# RFM232_V08_USB.net
KiCad netlist of a schematic drawn in Altium Designer
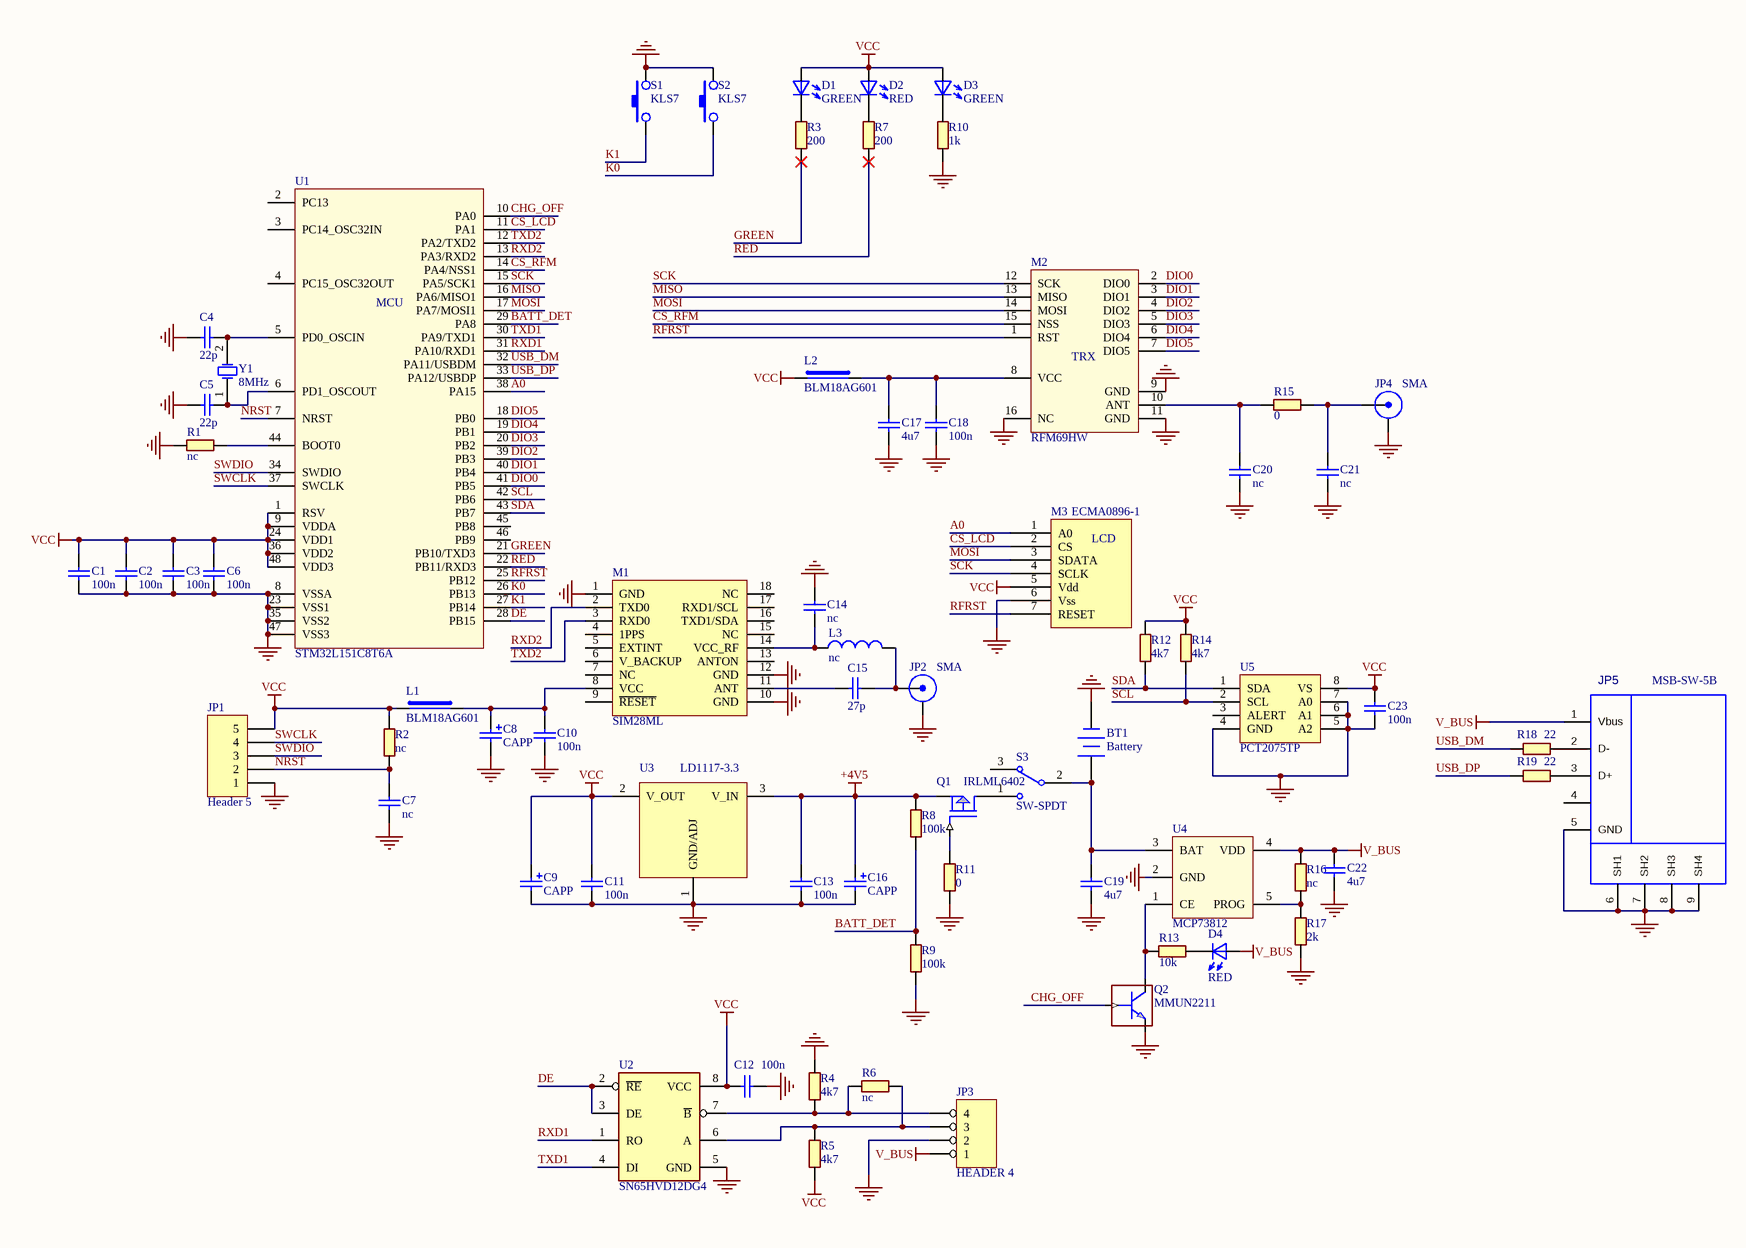
[diagram p0: RFM232_V08_USB.SchDoc]

(export (version "E")
  (design (tool "Eeschema 10.0.6"))
  (components
    (comp (ref "BT1")
      (value "Battery")
      (footprint "18650")
      (description "Multicell Battery")
      (fields (field (name "PUBLISHER") "Altium Limited"))
      (libsource (lib "Miscellaneous Devices") (part "Battery"))
    )
    (comp (ref "C1") (value "100n") (footprint "C-0603") (libsource (lib "Discrete") (part "CAPN")))
    (comp (ref "C2") (value "100n") (footprint "C-0603") (libsource (lib "Discrete") (part "CAPN")))
    (comp (ref "C3") (value "100n") (footprint "C-0603") (libsource (lib "Discrete") (part "CAPN")))
    (comp (ref "C4") (value "22p") (footprint "C-0603") (libsource (lib "Discrete") (part "CAPN")))
    (comp (ref "C5") (value "22p") (footprint "C-0603") (libsource (lib "Discrete") (part "CAPN")))
    (comp (ref "C6") (value "100n") (footprint "C-0603") (libsource (lib "Discrete") (part "CAPN")))
    (comp (ref "C7") (value "nc") (footprint "C-0603") (libsource (lib "Discrete") (part "CAPN")))
    (comp (ref "C8") (value "CAPP") (footprint "C-TANTAL-B") (libsource (lib "Discrete") (part "CAPP")))
    (comp (ref "C9") (value "CAPP") (footprint "C-TANTAL-B") (libsource (lib "Discrete") (part "CAPP")))
    (comp (ref "C10") (value "100n") (footprint "C-0603") (libsource (lib "Discrete") (part "CAPN")))
    (comp (ref "C11") (value "100n") (footprint "C-0603") (libsource (lib "Discrete") (part "CAPN")))
    (comp (ref "C12") (value "100n") (footprint "C-0603") (libsource (lib "Discrete") (part "CAPN")))
    (comp (ref "C13") (value "100n") (footprint "C-0603") (libsource (lib "Discrete") (part "CAPN")))
    (comp (ref "C14") (value "nc") (footprint "C-0603") (libsource (lib "Discrete") (part "CAPN")))
    (comp (ref "C15") (value "27p") (footprint "C-0603") (libsource (lib "Discrete") (part "CAPN")))
    (comp (ref "C16") (value "CAPP") (footprint "C-TANTAL-B") (libsource (lib "Discrete") (part "CAPP")))
    (comp (ref "C17") (value "4u7") (footprint "C-0805") (libsource (lib "Discrete") (part "CAPN")))
    (comp (ref "C18") (value "100n") (footprint "C-0603") (libsource (lib "Discrete") (part "CAPN")))
    (comp (ref "C19") (value "4u7") (footprint "C-0805") (libsource (lib "Discrete") (part "CAPN")))
    (comp (ref "C20") (value "nc") (footprint "C-0603") (libsource (lib "Discrete") (part "CAPN")))
    (comp (ref "C21") (value "nc") (footprint "C-0603") (libsource (lib "Discrete") (part "CAPN")))
    (comp (ref "C22") (value "4u7") (footprint "C-0805") (libsource (lib "Discrete") (part "CAPN")))
    (comp (ref "C23") (value "100n") (footprint "C-0603") (libsource (lib "Discrete") (part "CAPN")))
    (comp (ref "D1") (value "GREEN") (footprint "LED_0805") (libsource (lib "Discrete") (part "DLED")))
    (comp (ref "D2") (value "RED") (footprint "LED_0805") (libsource (lib "Discrete") (part "DLED")))
    (comp (ref "D3") (value "GREEN") (footprint "LED_0805") (libsource (lib "Discrete") (part "DLED")))
    (comp (ref "D4") (value "RED") (footprint "LED_0805") (libsource (lib "Discrete") (part "DLED")))
    (comp (ref "JP1")
      (value "Header 5")
      (footprint "PLS1-5R")
      (description "Header, 5-Pin")
      (fields (field (name "PUBLISHER") "Altium Limited"))
      (libsource (lib "Miscellaneous Connectors") (part "Header 5"))
    )
    (comp (ref "JP2")
      (value "SMA")
      (footprint "AMPHENOL_132357-11")
      (description "RF Connector")
      (libsource (lib "Connectors$switces") (part "X-004"))
    )
    (comp (ref "JP3")
      (value "HEADER 4")
      (footprint "PLS1-4")
      (description "4 Pin Header")
      (libsource (lib "Connectors$switces") (part "HEADER 4"))
    )
    (comp (ref "JP4")
      (value "SMA")
      (footprint "AMPHENOL_132357-11")
      (description "RF Connector")
      (libsource (lib "Connectors$switces") (part "X-004"))
    )
    (comp (ref "JP5")
      (value "MSB-SW-5B")
      (footprint "CU09SAM")
      (libsource (lib "XTRACK_v3.2") (part "MSB-SW-5B"))
    )
    (comp (ref "L1") (value "BLM18AG601") (footprint "L-0603") (libsource (lib "Discrete") (part "SUPRESOR")))
    (comp (ref "L2") (value "BLM18AG601") (footprint "L-0603") (libsource (lib "Discrete") (part "SUPRESOR")))
    (comp (ref "L3") (value "nc") (footprint "L-0603") (libsource (lib "Discrete") (part "L")))
    (comp (ref "M1")
      (value "SIM28ML")
      (footprint "LGA18_GNSS")
      (libsource (lib "Cellular_GNSS") (part "SIM28ML"))
    )
    (comp (ref "M2")
      (value "RFM69HW")
      (footprint "LGA16_RFM69")
      (libsource (lib "CLAP_M505_WL_BP_V22") (part "RFM69HW_V13_2"))
    )
    (comp (ref "M3") (value "ECMA0896-1") (footprint "PLS1-7") (libsource (lib "RCS-IMS") (part "ECMA0896")))
    (comp (ref "Q1") (value "IRLML6402") (footprint "SOT-23") (libsource (lib "Discrete") (part "IRLML6402")))
    (comp (ref "Q2") (value "MMUN2211") (footprint "SOT-23") (libsource (lib "Discrete") (part "MMUN2211")))
    (comp (ref "R1") (value "nc") (footprint "R-0603") (libsource (lib "") (part "RES_1")))
    (comp (ref "R2") (value "nc") (footprint "R-0603") (libsource (lib "Discrete") (part "RES")))
    (comp (ref "R3") (value "200") (footprint "R-0603") (libsource (lib "") (part "RES_3")))
    (comp (ref "R4") (value "4k7") (footprint "R-0603") (libsource (lib "Discrete") (part "RES")))
    (comp (ref "R5") (value "4k7") (footprint "R-0603") (libsource (lib "Discrete") (part "RES")))
    (comp (ref "R6") (value "nc") (footprint "R-0603") (libsource (lib "") (part "RES_2")))
    (comp (ref "R7") (value "200") (footprint "R-0603") (libsource (lib "") (part "RES_3")))
    (comp (ref "R8") (value "100k") (footprint "R-0603") (libsource (lib "Discrete") (part "RES")))
    (comp (ref "R9") (value "100k") (footprint "R-0603") (libsource (lib "Discrete") (part "RES")))
    (comp (ref "R10") (value "1k") (footprint "R-0603") (libsource (lib "") (part "RES_3")))
    (comp (ref "R11") (value "0") (footprint "R-0603") (libsource (lib "Discrete") (part "RES")))
    (comp (ref "R12") (value "4k7") (footprint "R-0603") (libsource (lib "Discrete") (part "RES")))
    (comp (ref "R13") (value "10k") (footprint "R-0603") (libsource (lib "") (part "RES_2")))
    (comp (ref "R14") (value "4k7") (footprint "R-0603") (libsource (lib "Discrete") (part "RES")))
    (comp (ref "R15") (value "0") (footprint "R-0603") (libsource (lib "") (part "RES_1")))
    (comp (ref "R16") (value "nc") (footprint "R-0603") (libsource (lib "Discrete") (part "RES")))
    (comp (ref "R17") (value "2k") (footprint "R-0603") (libsource (lib "Discrete") (part "RES")))
    (comp (ref "R18") (value "22") (footprint "R-0603") (libsource (lib "") (part "RES_2")))
    (comp (ref "R19") (value "22") (footprint "R-0603") (libsource (lib "") (part "RES_2")))
    (comp (ref "S1") (value "KLS7") (footprint "KLS7-TS3602") (libsource (lib "CLAP DM-WL-R2") (part "SW-1")))
    (comp (ref "S2") (value "KLS7") (footprint "KLS7-TS3602") (libsource (lib "CLAP DM-WL-R2") (part "SW-1")))
    (comp (ref "S3")
      (value "SW-SPDT")
      (footprint "SPDT_100mil")
      (description "SPDT Subminiature Toggle Switch, Right Angle Mounting, Vertical Actuation")
      (fields (field (name "PUBLISHER") "Altium Limited"))
      (libsource (lib "Miscellaneous Devices") (part "SW-SPDT"))
    )
    (comp (ref "U1")
      (value "STM32L151C8T6A")
      (footprint "LQFP-48")
      (libsource (lib "RFtest") (part "STM32L151C8T6"))
    )
    (comp (ref "U2") (value "SN65HVD12DG4") (footprint "SO8") (libsource (lib "ICs") (part "SN65HVD12DG4")))
    (comp (ref "U3")
      (value "LD1117-3.3")
      (footprint "SOT230P700X180-4N")
      (libsource (lib "SB") (part "LM1117_3.3"))
    )
    (comp (ref "U4") (value "MCP73812") (footprint "SOT-23-5") (libsource (lib "RFtest") (part "MCP73812")))
    (comp (ref "U5") (value "PCT2075TP") (footprint "SOT1069-2") (libsource (lib "UL2016_v2") (part "TMP75")))
    (comp (ref "Y1")
      (value "8MHz")
      (footprint "HC49_3.5mm")
      (description "Crystal Oscillator")
      (fields (field (name "PUBLISHER") "Altium Limited"))
      (libsource (lib "Miscellaneous Devices") (part "XTAL"))
    )
  )
  (nets
    (net (code "1") (name "+4V5") (class "Default")
      (node (ref "C13") (pin "1") (pinfunction "1_1") (pintype "passive"))
      (node (ref "C16") (pin "2") (pinfunction "2_2") (pintype "passive"))
      (node (ref "Q1") (pin "2") (pinfunction "SOURCE_2") (pintype "passive"))
      (node (ref "R8") (pin "2") (pinfunction "2_2") (pintype "passive"))
      (node (ref "U3") (pin "3") (pinfunction "V_IN_3") (pintype "passive"))
    )
    (net (code "2") (name "/A0") (class "Default")
      (node (ref "M3") (pin "1") (pinfunction "A0_1") (pintype "passive"))
      (node (ref "U1") (pin "38") (pinfunction "PA15_38") (pintype "passive"))
    )
    (net (code "3") (name "/BATT_DET") (class "Default")
      (node (ref "R8") (pin "1") (pinfunction "1_1") (pintype "passive"))
      (node (ref "R9") (pin "2") (pinfunction "2_2") (pintype "passive"))
      (node (ref "U1") (pin "29") (pinfunction "PA8_29") (pintype "passive"))
    )
    (net (code "4") (name "/CHG_OFF") (class "Default")
      (node (ref "Q2") (pin "1") (pinfunction "BASE_1") (pintype "input"))
      (node (ref "U1") (pin "10") (pinfunction "PA0_10") (pintype "passive"))
    )
    (net (code "5") (name "/CS_LCD") (class "Default")
      (node (ref "M3") (pin "2") (pinfunction "CS_2") (pintype "passive"))
      (node (ref "U1") (pin "11") (pinfunction "PA1_11") (pintype "passive"))
    )
    (net (code "6") (name "/CS_RFM") (class "Default")
      (node (ref "M2") (pin "15") (pinfunction "NSS_15") (pintype "passive"))
      (node (ref "U1") (pin "14") (pinfunction "PA4/NSS1_14") (pintype "passive"))
    )
    (net (code "7") (name "/DE") (class "Default")
      (node (ref "U1") (pin "28") (pinfunction "PB15_28") (pintype "passive"))
      (node (ref "U2") (pin "2") (pinfunction "~{RE}_2") (pintype "passive"))
      (node (ref "U2") (pin "3") (pinfunction "DE_3") (pintype "passive"))
    )
    (net (code "8") (name "/DIO0") (class "Default")
      (node (ref "M2") (pin "2") (pinfunction "DIO0_2") (pintype "passive"))
      (node (ref "U1") (pin "41") (pinfunction "PB5_41") (pintype "passive"))
    )
    (net (code "9") (name "/DIO1") (class "Default")
      (node (ref "M2") (pin "3") (pinfunction "DIO1_3") (pintype "passive"))
      (node (ref "U1") (pin "40") (pinfunction "PB4_40") (pintype "passive"))
    )
    (net (code "10") (name "/DIO2") (class "Default")
      (node (ref "M2") (pin "4") (pinfunction "DIO2_4") (pintype "passive"))
      (node (ref "U1") (pin "39") (pinfunction "PB3_39") (pintype "passive"))
    )
    (net (code "11") (name "/DIO3") (class "Default")
      (node (ref "M2") (pin "5") (pinfunction "DIO3_5") (pintype "passive"))
      (node (ref "U1") (pin "20") (pinfunction "PB2_20") (pintype "passive"))
    )
    (net (code "12") (name "/DIO4") (class "Default")
      (node (ref "M2") (pin "6") (pinfunction "DIO4_6") (pintype "passive"))
      (node (ref "U1") (pin "19") (pinfunction "PB1_19") (pintype "passive"))
    )
    (net (code "13") (name "/DIO5") (class "Default")
      (node (ref "M2") (pin "7") (pinfunction "DIO5_7") (pintype "passive"))
      (node (ref "U1") (pin "18") (pinfunction "PB0_18") (pintype "passive"))
    )
    (net (code "14") (name "/GREEN") (class "Default")
      (node (ref "R3") (pin "2") (pinfunction "2_2") (pintype "passive"))
      (node (ref "U1") (pin "21") (pinfunction "PB10/TXD3_21") (pintype "passive"))
    )
    (net (code "15") (name "/K0") (class "Default")
      (node (ref "S2") (pin "1") (pinfunction "1_1") (pintype "passive"))
      (node (ref "U1") (pin "26") (pinfunction "PB13_26") (pintype "passive"))
    )
    (net (code "16") (name "/K1") (class "Default")
      (node (ref "S1") (pin "1") (pinfunction "1_1") (pintype "passive"))
      (node (ref "U1") (pin "27") (pinfunction "PB14_27") (pintype "passive"))
    )
    (net (code "17") (name "/MISO") (class "Default")
      (node (ref "M2") (pin "13") (pinfunction "MISO_13") (pintype "passive"))
      (node (ref "U1") (pin "16") (pinfunction "PA6/MISO1_16") (pintype "passive"))
    )
    (net (code "18") (name "/MOSI") (class "Default")
      (node (ref "M2") (pin "14") (pinfunction "MOSI_14") (pintype "passive"))
      (node (ref "M3") (pin "3") (pinfunction "SDATA_3") (pintype "passive"))
      (node (ref "U1") (pin "17") (pinfunction "PA7/MOSI1_17") (pintype "passive"))
    )
    (net (code "19") (name "/NRST") (class "Default")
      (node (ref "C7") (pin "1") (pinfunction "1_1") (pintype "passive"))
      (node (ref "JP1") (pin "2") (pinfunction "2_2") (pintype "passive"))
      (node (ref "R2") (pin "1") (pinfunction "1_1") (pintype "passive"))
      (node (ref "U1") (pin "7") (pinfunction "NRST_7") (pintype "passive"))
    )
    (net (code "20") (name "/RED") (class "Default")
      (node (ref "R7") (pin "2") (pinfunction "2_2") (pintype "passive"))
      (node (ref "U1") (pin "22") (pinfunction "PB11/RXD3_22") (pintype "passive"))
    )
    (net (code "21") (name "/RFRST") (class "Default")
      (node (ref "M2") (pin "1") (pinfunction "RST_1") (pintype "passive"))
      (node (ref "M3") (pin "7") (pinfunction "RESET_7") (pintype "passive"))
      (node (ref "U1") (pin "25") (pinfunction "PB12_25") (pintype "passive"))
    )
    (net (code "22") (name "/RXD1") (class "Default")
      (node (ref "U1") (pin "31") (pinfunction "PA10/RXD1_31") (pintype "passive"))
      (node (ref "U2") (pin "1") (pinfunction "RO_1") (pintype "passive"))
    )
    (net (code "23") (name "/RXD2") (class "Default")
      (node (ref "M1") (pin "2") (pinfunction "TXD0_2") (pintype "passive"))
      (node (ref "U1") (pin "13") (pinfunction "PA3/RXD2_13") (pintype "passive"))
    )
    (net (code "24") (name "/SCK") (class "Default")
      (node (ref "M2") (pin "12") (pinfunction "SCK_12") (pintype "passive"))
      (node (ref "M3") (pin "4") (pinfunction "SCLK_4") (pintype "passive"))
      (node (ref "U1") (pin "15") (pinfunction "PA5/SCK1_15") (pintype "passive"))
    )
    (net (code "25") (name "/SCL") (class "Default")
      (node (ref "R14") (pin "1") (pinfunction "1_1") (pintype "passive"))
      (node (ref "U1") (pin "42") (pinfunction "PB6_42") (pintype "passive"))
      (node (ref "U5") (pin "2") (pinfunction "SCL_2") (pintype "passive"))
    )
    (net (code "26") (name "/SDA") (class "Default")
      (node (ref "R12") (pin "1") (pinfunction "1_1") (pintype "passive"))
      (node (ref "U1") (pin "43") (pinfunction "PB7_43") (pintype "passive"))
      (node (ref "U5") (pin "1") (pinfunction "SDA_1") (pintype "passive"))
    )
    (net (code "27") (name "/SWCLK") (class "Default")
      (node (ref "JP1") (pin "4") (pinfunction "4_4") (pintype "passive"))
      (node (ref "U1") (pin "37") (pinfunction "SWCLK_37") (pintype "passive"))
    )
    (net (code "28") (name "/SWDIO") (class "Default")
      (node (ref "JP1") (pin "3") (pinfunction "3_3") (pintype "passive"))
      (node (ref "U1") (pin "34") (pinfunction "SWDIO_34") (pintype "passive"))
    )
    (net (code "29") (name "/TXD1") (class "Default")
      (node (ref "U1") (pin "30") (pinfunction "PA9/TXD1_30") (pintype "passive"))
      (node (ref "U2") (pin "4") (pinfunction "DI_4") (pintype "passive"))
    )
    (net (code "30") (name "/TXD2") (class "Default")
      (node (ref "M1") (pin "3") (pinfunction "RXD0_3") (pintype "passive"))
      (node (ref "U1") (pin "12") (pinfunction "PA2/TXD2_12") (pintype "passive"))
    )
    (net (code "31") (name "/USB_DM") (class "Default")
      (node (ref "R18") (pin "2") (pinfunction "2_2") (pintype "passive"))
      (node (ref "U1") (pin "32") (pinfunction "PA11/USBDM_32") (pintype "passive"))
    )
    (net (code "32") (name "/USB_DP") (class "Default")
      (node (ref "R19") (pin "2") (pinfunction "2_2") (pintype "passive"))
      (node (ref "U1") (pin "33") (pinfunction "PA12/USBDP_33") (pintype "passive"))
    )
    (net (code "33") (name "GND") (class "Default")
      (node (ref "BT1") (pin "2") (pinfunction "-_2") (pintype "passive"))
      (node (ref "C1") (pin "2") (pinfunction "2_2") (pintype "passive"))
      (node (ref "C10") (pin "2") (pinfunction "2_2") (pintype "passive"))
      (node (ref "C11") (pin "2") (pinfunction "2_2") (pintype "passive"))
      (node (ref "C12") (pin "2") (pinfunction "2_2") (pintype "passive"))
      (node (ref "C13") (pin "2") (pinfunction "2_2") (pintype "passive"))
      (node (ref "C14") (pin "1") (pinfunction "1_1") (pintype "passive"))
      (node (ref "C16") (pin "1") (pinfunction "1_1") (pintype "passive"))
      (node (ref "C17") (pin "2") (pinfunction "2_2") (pintype "passive"))
      (node (ref "C18") (pin "2") (pinfunction "2_2") (pintype "passive"))
      (node (ref "C19") (pin "2") (pinfunction "2_2") (pintype "passive"))
      (node (ref "C2") (pin "2") (pinfunction "2_2") (pintype "passive"))
      (node (ref "C20") (pin "2") (pinfunction "2_2") (pintype "passive"))
      (node (ref "C21") (pin "2") (pinfunction "2_2") (pintype "passive"))
      (node (ref "C22") (pin "2") (pinfunction "2_2") (pintype "passive"))
      (node (ref "C23") (pin "2") (pinfunction "2_2") (pintype "passive"))
      (node (ref "C3") (pin "2") (pinfunction "2_2") (pintype "passive"))
      (node (ref "C4") (pin "1") (pinfunction "1_1") (pintype "passive"))
      (node (ref "C5") (pin "1") (pinfunction "1_1") (pintype "passive"))
      (node (ref "C6") (pin "2") (pinfunction "2_2") (pintype "passive"))
      (node (ref "C7") (pin "2") (pinfunction "2_2") (pintype "passive"))
      (node (ref "C8") (pin "1") (pinfunction "1_1") (pintype "passive"))
      (node (ref "C9") (pin "1") (pinfunction "1_1") (pintype "passive"))
      (node (ref "JP1") (pin "1") (pinfunction "1_1") (pintype "passive"))
      (node (ref "JP2") (pin "2") (pinfunction "Y_2") (pintype "passive"))
      (node (ref "JP3") (pin "2") (pinfunction "2_2") (pintype "passive"))
      (node (ref "JP4") (pin "2") (pinfunction "Y_2") (pintype "passive"))
      (node (ref "JP5") (pin "5") (pinfunction "GND_5") (pintype "passive"))
      (node (ref "JP5") (pin "6") (pinfunction "SH1_6") (pintype "passive"))
      (node (ref "JP5") (pin "7") (pinfunction "SH2_7") (pintype "passive"))
      (node (ref "JP5") (pin "8") (pinfunction "SH3_8") (pintype "passive"))
      (node (ref "JP5") (pin "9") (pinfunction "SH4_9") (pintype "passive"))
      (node (ref "M1") (pin "1") (pinfunction "GND_1") (pintype "passive"))
      (node (ref "M1") (pin "10") (pinfunction "GND_10") (pintype "passive"))
      (node (ref "M1") (pin "12") (pinfunction "GND_12") (pintype "passive"))
      (node (ref "M2") (pin "11") (pinfunction "GND_11") (pintype "passive"))
      (node (ref "M2") (pin "16") (pinfunction "NC_16") (pintype "passive"))
      (node (ref "M2") (pin "9") (pinfunction "GND_9") (pintype "passive"))
      (node (ref "M3") (pin "6") (pinfunction "Vss_6") (pintype "passive"))
      (node (ref "Q2") (pin "2") (pinfunction "EMITTER_2") (pintype "passive"))
      (node (ref "R1") (pin "1") (pinfunction "1_1") (pintype "passive"))
      (node (ref "R10") (pin "2") (pinfunction "2_2") (pintype "passive"))
      (node (ref "R11") (pin "1") (pinfunction "1_1") (pintype "passive"))
      (node (ref "R17") (pin "1") (pinfunction "1_1") (pintype "passive"))
      (node (ref "R4") (pin "2") (pinfunction "2_2") (pintype "passive"))
      (node (ref "R9") (pin "1") (pinfunction "1_1") (pintype "passive"))
      (node (ref "S1") (pin "2") (pinfunction "2_2") (pintype "passive"))
      (node (ref "S2") (pin "2") (pinfunction "2_2") (pintype "passive"))
      (node (ref "U1") (pin "23") (pinfunction "VSS1_23") (pintype "passive"))
      (node (ref "U1") (pin "35") (pinfunction "VSS2_35") (pintype "passive"))
      (node (ref "U1") (pin "47") (pinfunction "VSS3_47") (pintype "passive"))
      (node (ref "U1") (pin "8") (pinfunction "VSSA_8") (pintype "passive"))
      (node (ref "U2") (pin "5") (pinfunction "GND_5") (pintype "passive"))
      (node (ref "U3") (pin "1") (pinfunction "GND/ADJ_1") (pintype "passive"))
      (node (ref "U4") (pin "2") (pinfunction "GND_2") (pintype "passive"))
      (node (ref "U5") (pin "4") (pinfunction "GND_4") (pintype "passive"))
      (node (ref "U5") (pin "5") (pinfunction "A2_5") (pintype "passive"))
      (node (ref "U5") (pin "6") (pinfunction "A1_6") (pintype "passive"))
      (node (ref "U5") (pin "7") (pinfunction "A0_7") (pintype "passive"))
    )
    (net (code "34") (name "Net-(BT1-+)") (class "Default")
      (node (ref "BT1") (pin "1") (pinfunction "+_1") (pintype "passive"))
      (node (ref "C19") (pin "1") (pinfunction "1_1") (pintype "passive"))
      (node (ref "S3") (pin "2") (pinfunction "2_2") (pintype "passive"))
      (node (ref "U4") (pin "3") (pinfunction "BAT_3") (pintype "passive"))
    )
    (net (code "35") (name "Net-(D1-2)") (class "Default")
      (node (ref "D1") (pin "K") (pinfunction "2_K") (pintype "passive"))
      (node (ref "R3") (pin "1") (pinfunction "1_1") (pintype "passive"))
    )
    (net (code "36") (name "Net-(D2-2)") (class "Default")
      (node (ref "D2") (pin "K") (pinfunction "2_K") (pintype "passive"))
      (node (ref "R7") (pin "1") (pinfunction "1_1") (pintype "passive"))
    )
    (net (code "37") (name "Net-(D3-2)") (class "Default")
      (node (ref "D3") (pin "K") (pinfunction "2_K") (pintype "passive"))
      (node (ref "R10") (pin "1") (pinfunction "1_1") (pintype "passive"))
    )
    (net (code "38") (name "Net-(D4-2)") (class "Default")
      (node (ref "D4") (pin "K") (pinfunction "2_K") (pintype "passive"))
      (node (ref "R13") (pin "1") (pinfunction "1_1") (pintype "passive"))
    )
    (net (code "39") (name "Net-(JP2-X)") (class "Default")
      (node (ref "C15") (pin "2") (pinfunction "2_2") (pintype "passive"))
      (node (ref "JP2") (pin "1") (pinfunction "X_1") (pintype "passive"))
      (node (ref "L3") (pin "2") (pinfunction "2_2") (pintype "passive"))
    )
    (net (code "40") (name "Net-(JP4-X)") (class "Default")
      (node (ref "C21") (pin "1") (pinfunction "1_1") (pintype "passive"))
      (node (ref "JP4") (pin "1") (pinfunction "X_1") (pintype "passive"))
      (node (ref "R15") (pin "2") (pinfunction "2_2") (pintype "passive"))
    )
    (net (code "41") (name "Net-(JP5-D+)") (class "Default")
      (node (ref "JP5") (pin "3") (pinfunction "D+_3") (pintype "passive"))
      (node (ref "R19") (pin "1") (pinfunction "1_1") (pintype "passive"))
    )
    (net (code "42") (name "Net-(JP5-D-)") (class "Default")
      (node (ref "JP5") (pin "2") (pinfunction "D-_2") (pintype "passive"))
      (node (ref "R18") (pin "1") (pinfunction "1_1") (pintype "passive"))
    )
    (net (code "43") (name "Net-(M1-ANT)") (class "Default")
      (node (ref "C15") (pin "1") (pinfunction "1_1") (pintype "passive"))
      (node (ref "M1") (pin "11") (pinfunction "ANT_11") (pintype "passive"))
    )
    (net (code "44") (name "Net-(M1-VCC)") (class "Default")
      (node (ref "C10") (pin "1") (pinfunction "1_1") (pintype "passive"))
      (node (ref "C8") (pin "2") (pinfunction "2_2") (pintype "passive"))
      (node (ref "L1") (pin "2") (pinfunction "2_2") (pintype "passive"))
      (node (ref "M1") (pin "8") (pinfunction "VCC_8") (pintype "passive"))
    )
    (net (code "45") (name "Net-(M1-VCC_RF)") (class "Default")
      (node (ref "C14") (pin "2") (pinfunction "2_2") (pintype "passive"))
      (node (ref "L3") (pin "1") (pinfunction "1_1") (pintype "passive"))
      (node (ref "M1") (pin "14") (pinfunction "VCC_RF_14") (pintype "passive"))
    )
    (net (code "46") (name "Net-(M2-ANT)") (class "Default")
      (node (ref "C20") (pin "1") (pinfunction "1_1") (pintype "passive"))
      (node (ref "M2") (pin "10") (pinfunction "ANT_10") (pintype "passive"))
      (node (ref "R15") (pin "1") (pinfunction "1_1") (pintype "passive"))
    )
    (net (code "47") (name "Net-(M2-VCC)") (class "Default")
      (node (ref "C17") (pin "1") (pinfunction "1_1") (pintype "passive"))
      (node (ref "C18") (pin "1") (pinfunction "1_1") (pintype "passive"))
      (node (ref "L2") (pin "2") (pinfunction "2_2") (pintype "passive"))
      (node (ref "M2") (pin "8") (pinfunction "VCC_8") (pintype "passive"))
    )
    (net (code "48") (name "Net-(Q1-DRAIN)") (class "Default")
      (node (ref "Q1") (pin "3") (pinfunction "DRAIN_3") (pintype "passive"))
      (node (ref "S3") (pin "1") (pinfunction "1_1") (pintype "passive"))
    )
    (net (code "49") (name "Net-(Q1-GATE)") (class "Default")
      (node (ref "Q1") (pin "1") (pinfunction "GATE_1") (pintype "input"))
      (node (ref "R11") (pin "2") (pinfunction "2_2") (pintype "passive"))
    )
    (net (code "50") (name "Net-(Q2-COLLECTOR)") (class "Default")
      (node (ref "Q2") (pin "3") (pinfunction "COLLECTOR_3") (pintype "passive"))
      (node (ref "R13") (pin "2") (pinfunction "2_2") (pintype "passive"))
      (node (ref "U4") (pin "1") (pinfunction "CE_1") (pintype "passive"))
    )
    (net (code "51") (name "Net-(U1-BOOT0)") (class "Default")
      (node (ref "R1") (pin "2") (pinfunction "2_2") (pintype "passive"))
      (node (ref "U1") (pin "44") (pinfunction "BOOT0_44") (pintype "passive"))
    )
    (net (code "52") (name "Net-(U1-PD0_OSCIN)") (class "Default")
      (node (ref "C4") (pin "2") (pinfunction "2_2") (pintype "passive"))
      (node (ref "U1") (pin "5") (pinfunction "PD0_OSCIN_5") (pintype "passive"))
      (node (ref "Y1") (pin "2") (pinfunction "OSC2_2") (pintype "passive"))
    )
    (net (code "53") (name "Net-(U1-PD1_OSCOUT)") (class "Default")
      (node (ref "C5") (pin "2") (pinfunction "2_2") (pintype "passive"))
      (node (ref "U1") (pin "6") (pinfunction "PD1_OSCOUT_6") (pintype "passive"))
      (node (ref "Y1") (pin "1") (pinfunction "OSC1_1") (pintype "passive"))
    )
    (net (code "54") (name "Net-(U2-A)") (class "Default")
      (node (ref "JP3") (pin "3") (pinfunction "3_3") (pintype "passive"))
      (node (ref "R5") (pin "2") (pinfunction "2_2") (pintype "passive"))
      (node (ref "R6") (pin "1") (pinfunction "1_1") (pintype "passive"))
      (node (ref "U2") (pin "6") (pinfunction "A_6") (pintype "passive"))
    )
    (net (code "55") (name "Net-(U2-~{B})") (class "Default")
      (node (ref "JP3") (pin "4") (pinfunction "4_4") (pintype "passive"))
      (node (ref "R4") (pin "1") (pinfunction "1_1") (pintype "passive"))
      (node (ref "R6") (pin "2") (pinfunction "2_2") (pintype "passive"))
      (node (ref "U2") (pin "7") (pinfunction "~{B}_7") (pintype "passive"))
    )
    (net (code "56") (name "Net-(U4-PROG)") (class "Default")
      (node (ref "R16") (pin "1") (pinfunction "1_1") (pintype "passive"))
      (node (ref "R17") (pin "2") (pinfunction "2_2") (pintype "passive"))
      (node (ref "U4") (pin "5") (pinfunction "PROG_5") (pintype "passive"))
    )
    (net (code "57") (name "VCC") (class "Default")
      (node (ref "C1") (pin "1") (pinfunction "1_1") (pintype "passive"))
      (node (ref "C11") (pin "1") (pinfunction "1_1") (pintype "passive"))
      (node (ref "C12") (pin "1") (pinfunction "1_1") (pintype "passive"))
      (node (ref "C2") (pin "1") (pinfunction "1_1") (pintype "passive"))
      (node (ref "C23") (pin "1") (pinfunction "1_1") (pintype "passive"))
      (node (ref "C3") (pin "1") (pinfunction "1_1") (pintype "passive"))
      (node (ref "C6") (pin "1") (pinfunction "1_1") (pintype "passive"))
      (node (ref "C9") (pin "2") (pinfunction "2_2") (pintype "passive"))
      (node (ref "D1") (pin "A") (pinfunction "1_A") (pintype "passive"))
      (node (ref "D2") (pin "A") (pinfunction "1_A") (pintype "passive"))
      (node (ref "D3") (pin "A") (pinfunction "1_A") (pintype "passive"))
      (node (ref "JP1") (pin "5") (pinfunction "5_5") (pintype "passive"))
      (node (ref "L1") (pin "1") (pinfunction "1_1") (pintype "passive"))
      (node (ref "L2") (pin "1") (pinfunction "1_1") (pintype "passive"))
      (node (ref "M3") (pin "5") (pinfunction "Vdd_5") (pintype "passive"))
      (node (ref "R12") (pin "2") (pinfunction "2_2") (pintype "passive"))
      (node (ref "R14") (pin "2") (pinfunction "2_2") (pintype "passive"))
      (node (ref "R2") (pin "2") (pinfunction "2_2") (pintype "passive"))
      (node (ref "R5") (pin "1") (pinfunction "1_1") (pintype "passive"))
      (node (ref "U1") (pin "1") (pinfunction "RSV_1") (pintype "passive"))
      (node (ref "U1") (pin "24") (pinfunction "VDD1_24") (pintype "passive"))
      (node (ref "U1") (pin "36") (pinfunction "VDD2_36") (pintype "passive"))
      (node (ref "U1") (pin "48") (pinfunction "VDD3_48") (pintype "passive"))
      (node (ref "U1") (pin "9") (pinfunction "VDDA_9") (pintype "passive"))
      (node (ref "U2") (pin "8") (pinfunction "VCC_8") (pintype "passive"))
      (node (ref "U3") (pin "2") (pinfunction "V_OUT_2") (pintype "passive"))
      (node (ref "U5") (pin "8") (pinfunction "VS_8") (pintype "passive"))
    )
    (net (code "58") (name "V_BUS") (class "Default")
      (node (ref "C22") (pin "1") (pinfunction "1_1") (pintype "passive"))
      (node (ref "D4") (pin "A") (pinfunction "1_A") (pintype "passive"))
      (node (ref "JP3") (pin "1") (pinfunction "1_1") (pintype "passive"))
      (node (ref "JP5") (pin "1") (pinfunction "Vbus_1") (pintype "passive"))
      (node (ref "R16") (pin "2") (pinfunction "2_2") (pintype "passive"))
      (node (ref "U4") (pin "4") (pinfunction "VDD_4") (pintype "passive"))
    )
    (net (code "59") (name "unconnected-(JP5-Pad4)") (class "Default")
      (node (ref "JP5") (pin "4") (pintype "passive"))
    )
    (net (code "60") (name "unconnected-(M1-1PPS-Pad4)") (class "Default")
      (node (ref "M1") (pin "4") (pinfunction "1PPS_4") (pintype "passive"))
    )
    (net (code "61") (name "unconnected-(M1-ANTON-Pad13)") (class "Default")
      (node (ref "M1") (pin "13") (pinfunction "ANTON_13") (pintype "passive"))
    )
    (net (code "62") (name "unconnected-(M1-EXTINT-Pad5)") (class "Default")
      (node (ref "M1") (pin "5") (pinfunction "EXTINT_5") (pintype "passive"))
    )
    (net (code "63") (name "unconnected-(M1-NC-Pad7)") (class "Default")
      (node (ref "M1") (pin "7") (pinfunction "NC_7") (pintype "passive"))
    )
    (net (code "64") (name "unconnected-(M1-NC-Pad15)") (class "Default")
      (node (ref "M1") (pin "15") (pinfunction "NC_15") (pintype "passive"))
    )
    (net (code "65") (name "unconnected-(M1-NC-Pad18)") (class "Default")
      (node (ref "M1") (pin "18") (pinfunction "NC_18") (pintype "passive"))
    )
    (net (code "66") (name "unconnected-(M1-RXD1{slash}SCL-Pad17)") (class "Default")
      (node (ref "M1") (pin "17") (pinfunction "RXD1/SCL_17") (pintype "passive"))
    )
    (net (code "67") (name "unconnected-(M1-TXD1{slash}SDA-Pad16)") (class "Default")
      (node (ref "M1") (pin "16") (pinfunction "TXD1/SDA_16") (pintype "passive"))
    )
    (net (code "68") (name "unconnected-(M1-V_BACKUP-Pad6)") (class "Default")
      (node (ref "M1") (pin "6") (pinfunction "V_BACKUP_6") (pintype "passive"))
    )
    (net (code "69") (name "unconnected-(M1-~{RESET}-Pad9)") (class "Default")
      (node (ref "M1") (pin "9") (pinfunction "~{RESET}_9") (pintype "passive"))
    )
    (net (code "70") (name "unconnected-(S3-Pad3)") (class "Default")
      (node (ref "S3") (pin "3") (pinfunction "3_3") (pintype "passive"))
    )
    (net (code "71") (name "unconnected-(U1-PB8-Pad45)") (class "Default")
      (node (ref "U1") (pin "45") (pinfunction "PB8_45") (pintype "passive"))
    )
    (net (code "72") (name "unconnected-(U1-PB9-Pad46)") (class "Default")
      (node (ref "U1") (pin "46") (pinfunction "PB9_46") (pintype "passive"))
    )
    (net (code "73") (name "unconnected-(U1-PC13-Pad2)") (class "Default")
      (node (ref "U1") (pin "2") (pinfunction "PC13_2") (pintype "passive"))
    )
    (net (code "74") (name "unconnected-(U1-PC14_OSC32IN-Pad3)") (class "Default")
      (node (ref "U1") (pin "3") (pinfunction "PC14_OSC32IN_3") (pintype "passive"))
    )
    (net (code "75") (name "unconnected-(U1-PC15_OSC32OUT-Pad4)") (class "Default")
      (node (ref "U1") (pin "4") (pinfunction "PC15_OSC32OUT_4") (pintype "passive"))
    )
    (net (code "76") (name "unconnected-(U5-ALERT-Pad3)") (class "Default")
      (node (ref "U5") (pin "3") (pinfunction "ALERT_3") (pintype "passive"))
    )
  )
)
